# rf_d_door_lock.net
KiCad netlist of a schematic drawn in Altium Designer
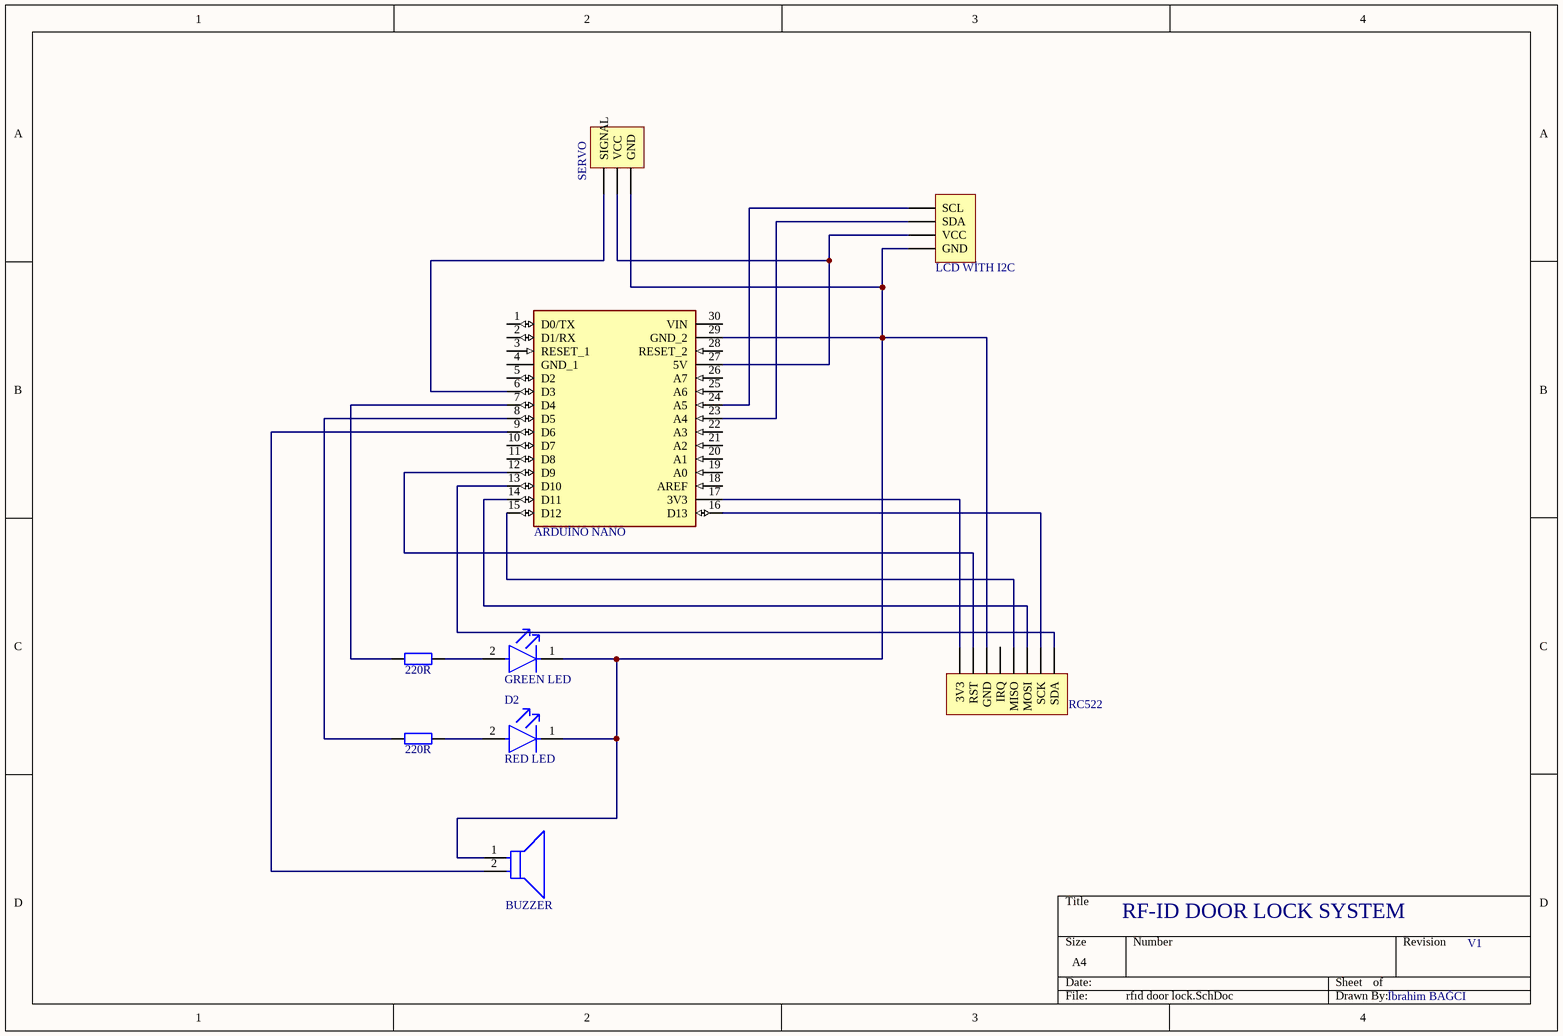
[diagram p0: rfıd door lock.SchDoc]

(export (version "E")
  (design (tool "Eeschema 10.0.6"))
  (components
    (comp (ref "D1")
      (value "GREEN LED")
      (footprint "FP-HLMP-1503-MFG")
      (description "LED GREEN DIFFUSED T-1 T/H")
      (fields (field (name "MANUFACTURER") "Broadcom") (field (name "MANUFACTURER PART NUMBER") "HLMP-1503"))
      (libsource (lib "Altium Content Vault") (part "8706943c75ba83719d021d2fdc84c58"))
    )
    (comp (ref "D2")
      (value "RED LED")
      (footprint "FP-HLMP-1301-MFG")
      (description "LED RED DIFFUSED T-1 T/H")
      (fields
        (field (name "MANUFACTURER PART NUMBER") "HLMP-1301")
        (field (name "OCTOPART") "https://octopart.com/hlmp-1301-broadcom-71130345")
      )
      (libsource (lib "Altium Content Vault") (part "8706943c75ba83719d021d2fdc84c58"))
    )
    (comp (ref "LS1")
      (value "BUZZER")
      (footprint "FP-MCKPX-G1203A-K4056-MFG")
      (description "MAGNETIC BUZZER AND TRANSDUCER - More Details")
      (fields
        (field (name "MANUFACTURER PART NUMBER") "MCKPX-G1203A-K4056")
        (field (name "MANUFACTURER") "Multicomp Pro")
      )
      (libsource (lib "Altium Content Vault") (part "1973c4b650225fd2ddacaff6b763965"))
    )
    (comp (ref "P1")
      (value "SERVO")
      (footprint "HDR1X3")
      (description "Header, 3-Pin")
      (fields (field (name "PUBLISHER") "Altium Limited"))
      (libsource (lib "Miscellaneous Connectors") (part "Header 3"))
    )
    (comp (ref "P2")
      (value "LCD WİTH I2C")
      (footprint "HDR1X4")
      (description "Header, 4-Pin")
      (fields (field (name "PUBLISHER") "Altium Limited"))
      (libsource (lib "Miscellaneous Connectors") (part "Header 4"))
    )
    (comp (ref "P3")
      (value "RC522")
      (footprint "HDR1X8")
      (description "Header, 8-Pin")
      (fields (field (name "PUBLISHER") "Altium Limited"))
      (libsource (lib "Miscellaneous Connectors") (part "Header 8"))
    )
    (comp (ref "R1")
      (value "220R")
      (footprint "AXIAL-0.4")
      (description "Resistor")
      (fields (field (name "PUBLISHER") "Altium Limited"))
      (libsource (lib "Miscellaneous Devices") (part "Res2"))
    )
    (comp (ref "R2")
      (value "220R")
      (footprint "AXIAL-0.4")
      (description "Resistor")
      (fields (field (name "PUBLISHER") "Altium Limited"))
      (libsource (lib "Miscellaneous Devices") (part "Res2"))
    )
    (comp (ref "U1")
      (value "ARDUİNO NANO")
      (footprint "MODULE_A000005")
      (description "CLOCK SAW OSCILLATOR SEAM7050 T&")
      (fields (field (name "MP") "A000005"))
      (libsource (lib "A000005") (part "A000005"))
    )
  )
  (nets
    (net (code "1") (name "Net-(D1-A)") (class "Default")
      (node (ref "D1") (pin "2") (pinfunction "A_2") (pintype "passive"))
      (node (ref "R1") (pin "2") (pinfunction "2_2") (pintype "passive"))
    )
    (net (code "2") (name "Net-(D1-C)") (class "Default")
      (node (ref "D1") (pin "1") (pinfunction "C_1") (pintype "passive"))
      (node (ref "D2") (pin "1") (pinfunction "C_1") (pintype "passive"))
      (node (ref "LS1") (pin "1") (pinfunction "C_1") (pintype "passive"))
      (node (ref "P1") (pin "3") (pinfunction "GND_3") (pintype "passive"))
      (node (ref "P2") (pin "4") (pinfunction "GND_4") (pintype "passive"))
      (node (ref "P3") (pin "6") (pinfunction "GND_6") (pintype "passive"))
      (node (ref "U1") (pin "29") (pinfunction "GND_2_29") (pintype "power_in"))
    )
    (net (code "3") (name "Net-(D2-A)") (class "Default")
      (node (ref "D2") (pin "2") (pinfunction "A_2") (pintype "passive"))
      (node (ref "R2") (pin "2") (pinfunction "2_2") (pintype "passive"))
    )
    (net (code "4") (name "Net-(LS1-A)") (class "Default")
      (node (ref "LS1") (pin "2") (pinfunction "A_2") (pintype "passive"))
      (node (ref "U1") (pin "9") (pinfunction "D6_9") (pintype "bidirectional"))
    )
    (net (code "5") (name "Net-(P1-SIGNAL)") (class "Default")
      (node (ref "P1") (pin "1") (pinfunction "SIGNAL_1") (pintype "passive"))
      (node (ref "U1") (pin "6") (pinfunction "D3_6") (pintype "bidirectional"))
    )
    (net (code "6") (name "Net-(P1-VCC)") (class "Default")
      (node (ref "P1") (pin "2") (pinfunction "VCC_2") (pintype "passive"))
      (node (ref "P2") (pin "3") (pinfunction "VCC_3") (pintype "passive"))
      (node (ref "U1") (pin "27") (pinfunction "5V_27") (pintype "power_in"))
    )
    (net (code "7") (name "Net-(P2-SCL)") (class "Default")
      (node (ref "P2") (pin "1") (pinfunction "SCL_1") (pintype "passive"))
      (node (ref "U1") (pin "24") (pinfunction "A5_24") (pintype "input"))
    )
    (net (code "8") (name "Net-(P2-SDA)") (class "Default")
      (node (ref "P2") (pin "2") (pinfunction "SDA_2") (pintype "passive"))
      (node (ref "U1") (pin "23") (pinfunction "A4_23") (pintype "input"))
    )
    (net (code "9") (name "Net-(P3-3V3)") (class "Default")
      (node (ref "P3") (pin "8") (pinfunction "3V3_8") (pintype "passive"))
      (node (ref "U1") (pin "17") (pinfunction "3V3_17") (pintype "power_in"))
    )
    (net (code "10") (name "Net-(P3-MISO)") (class "Default")
      (node (ref "P3") (pin "4") (pinfunction "MISO_4") (pintype "passive"))
      (node (ref "U1") (pin "15") (pinfunction "D12_15") (pintype "bidirectional"))
    )
    (net (code "11") (name "Net-(P3-MOSI)") (class "Default")
      (node (ref "P3") (pin "3") (pinfunction "MOSI_3") (pintype "passive"))
      (node (ref "U1") (pin "14") (pinfunction "D11_14") (pintype "bidirectional"))
    )
    (net (code "12") (name "Net-(P3-RST)") (class "Default")
      (node (ref "P3") (pin "7") (pinfunction "RST_7") (pintype "passive"))
      (node (ref "U1") (pin "12") (pinfunction "D9_12") (pintype "bidirectional"))
    )
    (net (code "13") (name "Net-(P3-SCK)") (class "Default")
      (node (ref "P3") (pin "2") (pinfunction "SCK_2") (pintype "passive"))
      (node (ref "U1") (pin "16") (pinfunction "D13_16") (pintype "bidirectional"))
    )
    (net (code "14") (name "Net-(P3-SDA)") (class "Default")
      (node (ref "P3") (pin "1") (pinfunction "SDA_1") (pintype "passive"))
      (node (ref "U1") (pin "13") (pinfunction "D10_13") (pintype "bidirectional"))
    )
    (net (code "15") (name "Net-(U1-D4)") (class "Default")
      (node (ref "R1") (pin "1") (pinfunction "1_1") (pintype "passive"))
      (node (ref "U1") (pin "7") (pinfunction "D4_7") (pintype "bidirectional"))
    )
    (net (code "16") (name "Net-(U1-D5)") (class "Default")
      (node (ref "R2") (pin "1") (pinfunction "1_1") (pintype "passive"))
      (node (ref "U1") (pin "8") (pinfunction "D5_8") (pintype "bidirectional"))
    )
    (net (code "17") (name "unconnected-(P3-IRQ-Pad5)") (class "Default")
      (node (ref "P3") (pin "5") (pinfunction "IRQ_5") (pintype "passive"))
    )
    (net (code "18") (name "unconnected-(U1-A0-Pad19)") (class "Default")
      (node (ref "U1") (pin "19") (pinfunction "A0_19") (pintype "input"))
    )
    (net (code "19") (name "unconnected-(U1-A1-Pad20)") (class "Default")
      (node (ref "U1") (pin "20") (pinfunction "A1_20") (pintype "input"))
    )
    (net (code "20") (name "unconnected-(U1-A2-Pad21)") (class "Default")
      (node (ref "U1") (pin "21") (pinfunction "A2_21") (pintype "input"))
    )
    (net (code "21") (name "unconnected-(U1-A3-Pad22)") (class "Default")
      (node (ref "U1") (pin "22") (pinfunction "A3_22") (pintype "input"))
    )
    (net (code "22") (name "unconnected-(U1-A6-Pad25)") (class "Default")
      (node (ref "U1") (pin "25") (pinfunction "A6_25") (pintype "input"))
    )
    (net (code "23") (name "unconnected-(U1-A7-Pad26)") (class "Default")
      (node (ref "U1") (pin "26") (pinfunction "A7_26") (pintype "input"))
    )
    (net (code "24") (name "unconnected-(U1-AREF-Pad18)") (class "Default")
      (node (ref "U1") (pin "18") (pinfunction "AREF_18") (pintype "input"))
    )
    (net (code "25") (name "unconnected-(U1-D0{slash}TX-Pad1)") (class "Default")
      (node (ref "U1") (pin "1") (pinfunction "D0/TX_1") (pintype "bidirectional"))
    )
    (net (code "26") (name "unconnected-(U1-D1{slash}RX-Pad2)") (class "Default")
      (node (ref "U1") (pin "2") (pinfunction "D1/RX_2") (pintype "bidirectional"))
    )
    (net (code "27") (name "unconnected-(U1-D2-Pad5)") (class "Default")
      (node (ref "U1") (pin "5") (pinfunction "D2_5") (pintype "bidirectional"))
    )
    (net (code "28") (name "unconnected-(U1-D7-Pad10)") (class "Default")
      (node (ref "U1") (pin "10") (pinfunction "D7_10") (pintype "bidirectional"))
    )
    (net (code "29") (name "unconnected-(U1-D8-Pad11)") (class "Default")
      (node (ref "U1") (pin "11") (pinfunction "D8_11") (pintype "bidirectional"))
    )
    (net (code "30") (name "unconnected-(U1-GND_1-Pad4)") (class "Default")
      (node (ref "U1") (pin "4") (pinfunction "GND_1_4") (pintype "power_in"))
    )
    (net (code "31") (name "unconnected-(U1-RESET_1-Pad3)") (class "Default")
      (node (ref "U1") (pin "3") (pinfunction "RESET_1_3") (pintype "input"))
    )
    (net (code "32") (name "unconnected-(U1-RESET_2-Pad28)") (class "Default")
      (node (ref "U1") (pin "28") (pinfunction "RESET_2_28") (pintype "input"))
    )
    (net (code "33") (name "unconnected-(U1-VIN-Pad30)") (class "Default")
      (node (ref "U1") (pin "30") (pinfunction "VIN_30") (pintype "power_in"))
    )
  )
)
